# hdmi.net
KiCad netlist of a schematic drawn in Altium Designer
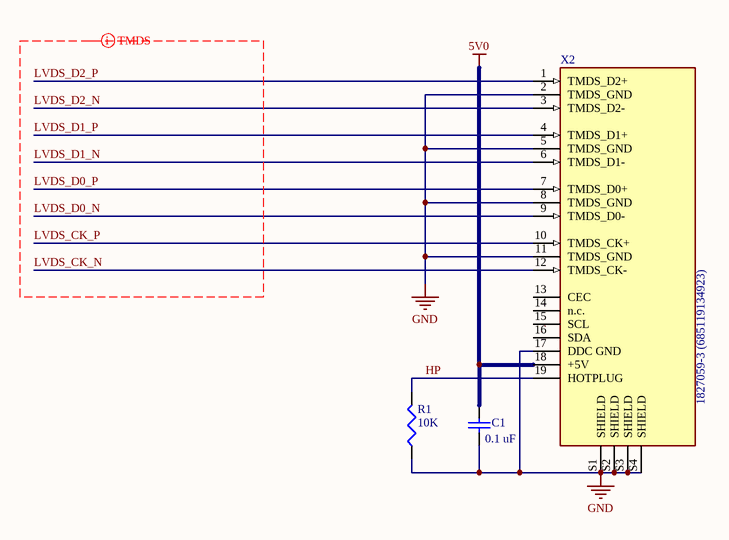
[diagram p0: hdmi.SchDoc]

(export (version "E")
  (design (tool "Eeschema 10.0.6"))
  (components
    (comp (ref "C1")
      (value "0.1 uF")
      (footprint "0805 chip cap")
      (description "Capacitor")
      (libsource (lib "Schlib") (part "Cap"))
    )
    (comp (ref "R1")
      (value "10K")
      (footprint "0805 CHIP RES")
      (description "Resistor")
      (libsource (lib "Schlib") (part "CHIP RES"))
    )
    (comp (ref "X2")
      (value "1827059-3 (685119134923)")
      (footprint "1827059-3 (685119134923)")
      (fields (field (name "MP") "SS-53000-001") (field (name "MF") "Stewart Connector"))
      (libsource (lib "Schlib") (part "1827059-3 (685119134923)"))
    )
  )
  (nets
    (net (code "1") (name "/HP") (class "Default")
      (node (ref "R1") (pin "2") (pinfunction "2_2") (pintype "passive"))
      (node (ref "X2") (pin "19") (pinfunction "HOTPLUG_19") (pintype "passive"))
    )
    (net (code "2") (name "/LVDS_CK_N") (class "Default")
      (node (ref "X2") (pin "12") (pinfunction "TMDS_CK-_12") (pintype "input"))
    )
    (net (code "3") (name "/LVDS_CK_P") (class "Default")
      (node (ref "X2") (pin "10") (pinfunction "TMDS_CK+_10") (pintype "input"))
    )
    (net (code "4") (name "/LVDS_D0_N") (class "Default")
      (node (ref "X2") (pin "9") (pinfunction "TMDS_D0-_9") (pintype "input"))
    )
    (net (code "5") (name "/LVDS_D0_P") (class "Default")
      (node (ref "X2") (pin "7") (pinfunction "TMDS_D0+_7") (pintype "input"))
    )
    (net (code "6") (name "/LVDS_D1_N") (class "Default")
      (node (ref "X2") (pin "6") (pinfunction "TMDS_D1-_6") (pintype "input"))
    )
    (net (code "7") (name "/LVDS_D1_P") (class "Default")
      (node (ref "X2") (pin "4") (pinfunction "TMDS_D1+_4") (pintype "input"))
    )
    (net (code "8") (name "/LVDS_D2_N") (class "Default")
      (node (ref "X2") (pin "3") (pinfunction "TMDS_D2-_3") (pintype "input"))
    )
    (net (code "9") (name "/LVDS_D2_P") (class "Default")
      (node (ref "X2") (pin "1") (pinfunction "TMDS_D2+_1") (pintype "input"))
    )
    (net (code "10") (name "5V0") (class "Default")
      (node (ref "C1") (pin "2") (pinfunction "2_2") (pintype "passive"))
      (node (ref "X2") (pin "18") (pinfunction "+5V_18") (pintype "passive"))
    )
    (net (code "11") (name "GND") (class "Default")
      (node (ref "C1") (pin "1") (pinfunction "1_1") (pintype "passive"))
      (node (ref "R1") (pin "1") (pinfunction "1_1") (pintype "passive"))
      (node (ref "X2") (pin "11") (pinfunction "TMDS_GND_11") (pintype "power_in"))
      (node (ref "X2") (pin "17") (pinfunction "DDC_GND_17") (pintype "passive"))
      (node (ref "X2") (pin "2") (pinfunction "TMDS_GND_2") (pintype "power_in"))
      (node (ref "X2") (pin "5") (pinfunction "TMDS_GND_5") (pintype "power_in"))
      (node (ref "X2") (pin "8") (pinfunction "TMDS_GND_8") (pintype "power_in"))
      (node (ref "X2") (pin "S1") (pinfunction "SHIELD_S1") (pintype "passive"))
      (node (ref "X2") (pin "S2") (pinfunction "SHIELD_S2") (pintype "passive"))
      (node (ref "X2") (pin "S3") (pinfunction "SHIELD_S3") (pintype "passive"))
      (node (ref "X2") (pin "S4") (pinfunction "SHIELD_S4") (pintype "passive"))
    )
    (net (code "12") (name "unconnected-(X2-CEC-Pad13)") (class "Default")
      (node (ref "X2") (pin "13") (pinfunction "CEC_13") (pintype "passive"))
    )
    (net (code "13") (name "unconnected-(X2-SCL-Pad15)") (class "Default")
      (node (ref "X2") (pin "15") (pinfunction "SCL_15") (pintype "passive"))
    )
    (net (code "14") (name "unconnected-(X2-SDA-Pad16)") (class "Default")
      (node (ref "X2") (pin "16") (pinfunction "SDA_16") (pintype "passive"))
    )
    (net (code "15") (name "unconnected-(X2-n.c.-Pad14)") (class "Default")
      (node (ref "X2") (pin "14") (pinfunction "n.c._14") (pintype "passive"))
    )
  )
)
